# Feather-M0-RAK811-SMA.net
KiCad netlist of a schematic drawn in EAGLE
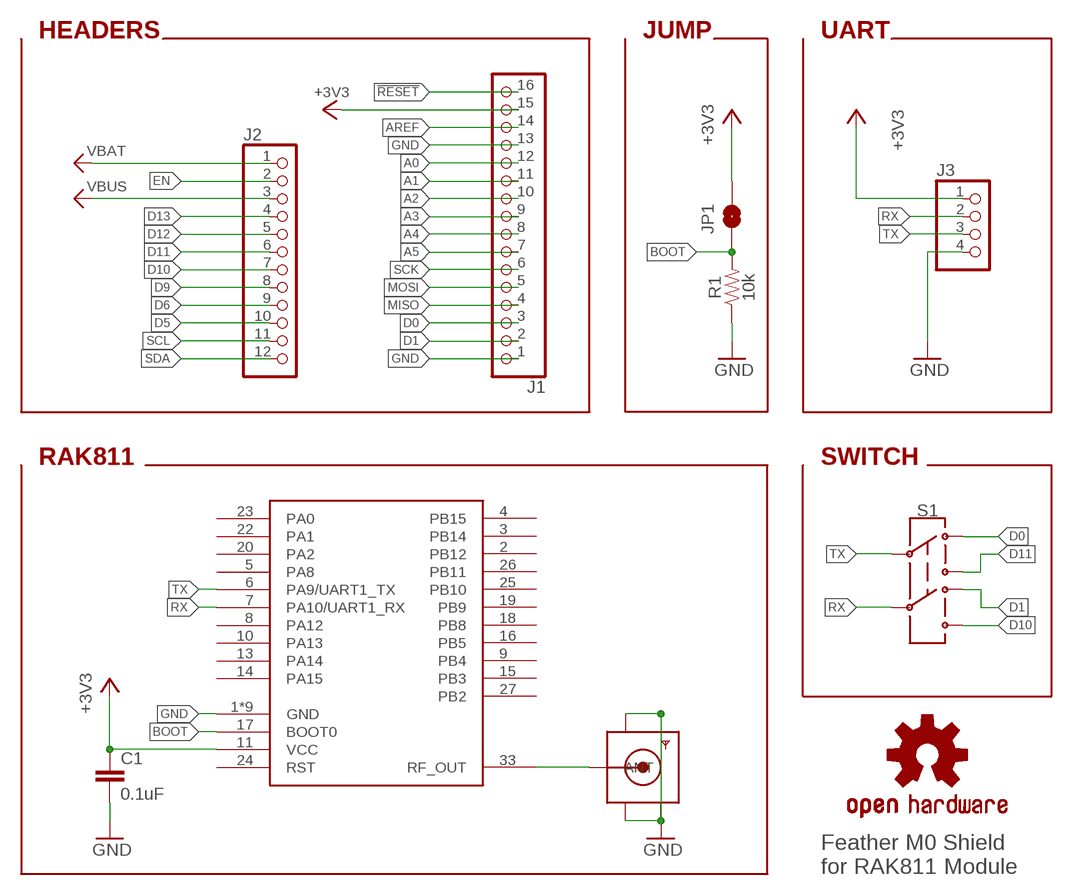
[diagram p0: schematic, sheet 1]

(export (version "E")
  (design (tool "Eeschema 10.0.6"))
  (components
    (comp (ref "C1")
      (value "0.1uF")
      (footprint "eagle-import:0603")
      (libsource (lib "eagle-import") (part "0.1UF-0603-25V-(+80/-20%)"))
    )
    (comp (ref "J1")
      (value "HEADER-1X16ROUND")
      (footprint "eagle-import:1X16_ROUND")
      (libsource (lib "eagle-import") (part "HEADER-1X16ROUND"))
    )
    (comp (ref "J2")
      (value "HEADER-1X12")
      (footprint "eagle-import:1X12_ROUND")
      (libsource (lib "eagle-import") (part "HEADER-1X12"))
    )
    (comp (ref "J3")
      (value "HEADER-1X4ROUND")
      (footprint "eagle-import:1X04_ROUND")
      (libsource (lib "eagle-import") (part "HEADER-1X4ROUND"))
    )
    (comp (ref "JP1")
      (value "JUMPER-SMT_2_NO_SILK")
      (footprint "eagle-import:SMT-JUMPER_2_NO_SILK")
      (libsource (lib "eagle-import") (part "JUMPER-SMT_2_NO_SILK"))
    )
    (comp (ref "LOGO1")
      (value "OSHW-LOGOS")
      (footprint "eagle-import:OSHW-LOGO-S")
      (libsource (lib "eagle-import") (part "OSHW-LOGOS"))
    )
    (comp (ref "R1")
      (value "10k")
      (footprint "eagle-import:0603")
      (libsource (lib "eagle-import") (part "10KOHM-0603-1/10W-1%"))
    )
    (comp (ref "S1")
      (value "SWITCH-DPDT-SMD-AYZ0202")
      (footprint "eagle-import:SWITCH_DPDT_SMD_AYZ0202")
      (libsource (lib "eagle-import") (part "SWITCH-DPDT-SMD-AYZ0202"))
    )
    (comp (ref "U1")
      (value "RAK_WIRELESS_RAK811")
      (footprint "eagle-import:RAK_WIRELESS_RAK811")
      (libsource (lib "eagle-import") (part "RAK_WIRELESS_RAK811"))
    )
    (comp (ref "X1")
      (value "SMACONNECTOR_EDGE")
      (footprint "eagle-import:SMA_EDGELAUNCH")
      (libsource (lib "eagle-import") (part "SMACONNECTOR_EDGE"))
    )
  )
  (nets
    (net (code "1") (name "+3V3") (class "Default")
      (node (ref "C1") (pin "1") (pinfunction "1_1") (pintype "passive"))
      (node (ref "J1") (pin "15") (pinfunction "15_15") (pintype "passive"))
      (node (ref "J3") (pin "1") (pinfunction "1_1") (pintype "passive"))
      (node (ref "JP1") (pin "2") (pinfunction "2_2") (pintype "passive"))
      (node (ref "U1") (pin "11") (pinfunction "VCC_11") (pintype "power_in"))
    )
    (net (code "2") (name "/~{RESET}") (class "Default")
      (node (ref "J1") (pin "16") (pinfunction "16_16") (pintype "passive"))
    )
    (net (code "3") (name "A0") (class "Default")
      (node (ref "J1") (pin "12") (pinfunction "12_12") (pintype "passive"))
    )
    (net (code "4") (name "A1") (class "Default")
      (node (ref "J1") (pin "11") (pinfunction "11_11") (pintype "passive"))
    )
    (net (code "5") (name "A2") (class "Default")
      (node (ref "J1") (pin "10") (pinfunction "10_10") (pintype "passive"))
    )
    (net (code "6") (name "A3") (class "Default")
      (node (ref "J1") (pin "9") (pinfunction "9_9") (pintype "passive"))
    )
    (net (code "7") (name "A4") (class "Default")
      (node (ref "J1") (pin "8") (pinfunction "8_8") (pintype "passive"))
    )
    (net (code "8") (name "A5") (class "Default")
      (node (ref "J1") (pin "7") (pinfunction "7_7") (pintype "passive"))
    )
    (net (code "9") (name "AREF") (class "Default")
      (node (ref "J1") (pin "14") (pinfunction "14_14") (pintype "passive"))
    )
    (net (code "10") (name "BOOT") (class "Default")
      (node (ref "JP1") (pin "1") (pinfunction "1_1") (pintype "passive"))
      (node (ref "R1") (pin "2") (pinfunction "2_2") (pintype "passive"))
      (node (ref "U1") (pin "17") (pinfunction "BOOT0_17") (pintype "input"))
    )
    (net (code "11") (name "D0") (class "Default")
      (node (ref "J1") (pin "3") (pinfunction "3_3") (pintype "passive"))
      (node (ref "S1") (pin "1") (pinfunction "1_1") (pintype "bidirectional"))
    )
    (net (code "12") (name "D1") (class "Default")
      (node (ref "J1") (pin "2") (pinfunction "2_2") (pintype "passive"))
      (node (ref "S1") (pin "4") (pinfunction "4_4") (pintype "bidirectional"))
    )
    (net (code "13") (name "D5") (class "Default")
      (node (ref "J2") (pin "10") (pinfunction "10_10") (pintype "passive"))
    )
    (net (code "14") (name "D6") (class "Default")
      (node (ref "J2") (pin "9") (pinfunction "9_9") (pintype "passive"))
    )
    (net (code "15") (name "D9") (class "Default")
      (node (ref "J2") (pin "8") (pinfunction "8_8") (pintype "passive"))
    )
    (net (code "16") (name "D10") (class "Default")
      (node (ref "J2") (pin "7") (pinfunction "7_7") (pintype "passive"))
      (node (ref "S1") (pin "6") (pinfunction "6_6") (pintype "bidirectional"))
    )
    (net (code "17") (name "D11") (class "Default")
      (node (ref "J2") (pin "6") (pinfunction "6_6") (pintype "passive"))
      (node (ref "S1") (pin "3") (pinfunction "3_3") (pintype "bidirectional"))
    )
    (net (code "18") (name "D12") (class "Default")
      (node (ref "J2") (pin "5") (pinfunction "5_5") (pintype "passive"))
    )
    (net (code "19") (name "D13") (class "Default")
      (node (ref "J2") (pin "4") (pinfunction "4_4") (pintype "passive"))
    )
    (net (code "20") (name "EN") (class "Default")
      (node (ref "J2") (pin "2") (pinfunction "2_2") (pintype "passive"))
    )
    (net (code "21") (name "GND") (class "Default")
      (node (ref "C1") (pin "2") (pinfunction "2_2") (pintype "passive"))
      (node (ref "J1") (pin "1") (pinfunction "1_1") (pintype "passive"))
      (node (ref "J1") (pin "13") (pinfunction "13_13") (pintype "passive"))
      (node (ref "J3") (pin "4") (pinfunction "4_4") (pintype "passive"))
      (node (ref "R1") (pin "1") (pinfunction "1_1") (pintype "passive"))
      (node (ref "U1") (pin "1") (pinfunction "GND_1") (pintype "power_in"))
      (node (ref "U1") (pin "12") (pinfunction "GND_12") (pintype "power_in"))
      (node (ref "U1") (pin "21") (pinfunction "GND_21") (pintype "power_in"))
      (node (ref "U1") (pin "28") (pinfunction "GND_28") (pintype "power_in"))
      (node (ref "U1") (pin "29") (pinfunction "GND_29") (pintype "power_in"))
      (node (ref "U1") (pin "30") (pinfunction "GND_30") (pintype "power_in"))
      (node (ref "U1") (pin "31") (pinfunction "GND_31") (pintype "power_in"))
      (node (ref "U1") (pin "32") (pinfunction "GND_32") (pintype "power_in"))
      (node (ref "U1") (pin "34") (pinfunction "GND_34") (pintype "power_in"))
      (node (ref "X1") (pin "GND@1") (pinfunction "GND4_GND@1") (pintype "power_in"))
      (node (ref "X1") (pin "GND@2") (pinfunction "GND3_GND@2") (pintype "power_in"))
      (node (ref "X1") (pin "GND@3") (pinfunction "GND2_GND@3") (pintype "power_in"))
      (node (ref "X1") (pin "GND@4") (pinfunction "GND1_GND@4") (pintype "power_in"))
    )
    (net (code "22") (name "MISO") (class "Default")
      (node (ref "J1") (pin "4") (pinfunction "4_4") (pintype "passive"))
    )
    (net (code "23") (name "MOSI") (class "Default")
      (node (ref "J1") (pin "5") (pinfunction "5_5") (pintype "passive"))
    )
    (net (code "24") (name "Net-(U1-RF_OUT)") (class "Default")
      (node (ref "U1") (pin "33") (pinfunction "RF_OUT_33") (pintype "bidirectional"))
      (node (ref "X1") (pin "P") (pinfunction "ANT_P") (pintype "bidirectional"))
    )
    (net (code "25") (name "RX") (class "Default")
      (node (ref "J3") (pin "2") (pinfunction "2_2") (pintype "passive"))
      (node (ref "S1") (pin "5") (pinfunction "5_5") (pintype "bidirectional"))
      (node (ref "U1") (pin "7") (pinfunction "PA10/UART1_RX_7") (pintype "input"))
    )
    (net (code "26") (name "SCK") (class "Default")
      (node (ref "J1") (pin "6") (pinfunction "6_6") (pintype "passive"))
    )
    (net (code "27") (name "SCL") (class "Default")
      (node (ref "J2") (pin "11") (pinfunction "11_11") (pintype "passive"))
    )
    (net (code "28") (name "SDA") (class "Default")
      (node (ref "J2") (pin "12") (pinfunction "12_12") (pintype "passive"))
    )
    (net (code "29") (name "TX") (class "Default")
      (node (ref "J3") (pin "3") (pinfunction "3_3") (pintype "passive"))
      (node (ref "S1") (pin "2") (pinfunction "2_2") (pintype "bidirectional"))
      (node (ref "U1") (pin "6") (pinfunction "PA9/UART1_TX_6") (pintype "bidirectional"))
    )
    (net (code "30") (name "VBAT") (class "Default")
      (node (ref "J2") (pin "1") (pinfunction "1_1") (pintype "passive"))
    )
    (net (code "31") (name "VBUS") (class "Default")
      (node (ref "J2") (pin "3") (pinfunction "3_3") (pintype "passive"))
    )
    (net (code "32") (name "unconnected-(U1-PA0-Pad23)") (class "Default")
      (node (ref "U1") (pin "23") (pinfunction "PA0_23") (pintype "bidirectional"))
    )
    (net (code "33") (name "unconnected-(U1-PA1-Pad22)") (class "Default")
      (node (ref "U1") (pin "22") (pinfunction "PA1_22") (pintype "input"))
    )
    (net (code "34") (name "unconnected-(U1-PA2-Pad20)") (class "Default")
      (node (ref "U1") (pin "20") (pinfunction "PA2_20") (pintype "bidirectional"))
    )
    (net (code "35") (name "unconnected-(U1-PA8-Pad5)") (class "Default")
      (node (ref "U1") (pin "5") (pinfunction "PA8_5") (pintype "bidirectional"))
    )
    (net (code "36") (name "unconnected-(U1-PA12-Pad8)") (class "Default")
      (node (ref "U1") (pin "8") (pinfunction "PA12_8") (pintype "bidirectional"))
    )
    (net (code "37") (name "unconnected-(U1-PA13-Pad10)") (class "Default")
      (node (ref "U1") (pin "10") (pinfunction "PA13_10") (pintype "bidirectional"))
    )
    (net (code "38") (name "unconnected-(U1-PA14-Pad13)") (class "Default")
      (node (ref "U1") (pin "13") (pinfunction "PA14_13") (pintype "bidirectional"))
    )
    (net (code "39") (name "unconnected-(U1-PA15-Pad14)") (class "Default")
      (node (ref "U1") (pin "14") (pinfunction "PA15_14") (pintype "bidirectional"))
    )
    (net (code "40") (name "unconnected-(U1-PB2-Pad27)") (class "Default")
      (node (ref "U1") (pin "27") (pinfunction "PB2_27") (pintype "bidirectional"))
    )
    (net (code "41") (name "unconnected-(U1-PB3-Pad15)") (class "Default")
      (node (ref "U1") (pin "15") (pinfunction "PB3_15") (pintype "bidirectional"))
    )
    (net (code "42") (name "unconnected-(U1-PB4-Pad9)") (class "Default")
      (node (ref "U1") (pin "9") (pinfunction "PB4_9") (pintype "input"))
    )
    (net (code "43") (name "unconnected-(U1-PB5-Pad16)") (class "Default")
      (node (ref "U1") (pin "16") (pinfunction "PB5_16") (pintype "bidirectional"))
    )
    (net (code "44") (name "unconnected-(U1-PB8-Pad18)") (class "Default")
      (node (ref "U1") (pin "18") (pinfunction "PB8_18") (pintype "bidirectional"))
    )
    (net (code "45") (name "unconnected-(U1-PB9-Pad19)") (class "Default")
      (node (ref "U1") (pin "19") (pinfunction "PB9_19") (pintype "bidirectional"))
    )
    (net (code "46") (name "unconnected-(U1-PB10-Pad25)") (class "Default")
      (node (ref "U1") (pin "25") (pinfunction "PB10_25") (pintype "bidirectional"))
    )
    (net (code "47") (name "unconnected-(U1-PB11-Pad26)") (class "Default")
      (node (ref "U1") (pin "26") (pinfunction "PB11_26") (pintype "bidirectional"))
    )
    (net (code "48") (name "unconnected-(U1-PB12-Pad2)") (class "Default")
      (node (ref "U1") (pin "2") (pinfunction "PB12_2") (pintype "bidirectional"))
    )
    (net (code "49") (name "unconnected-(U1-PB14-Pad3)") (class "Default")
      (node (ref "U1") (pin "3") (pinfunction "PB14_3") (pintype "bidirectional"))
    )
    (net (code "50") (name "unconnected-(U1-PB15-Pad4)") (class "Default")
      (node (ref "U1") (pin "4") (pinfunction "PB15_4") (pintype "bidirectional"))
    )
    (net (code "51") (name "unconnected-(U1-RST-Pad24)") (class "Default")
      (node (ref "U1") (pin "24") (pinfunction "RST_24") (pintype "input"))
    )
  )
)
